# VIDCEnhancer.net
KiCad netlist of a schematic drawn in EAGLE
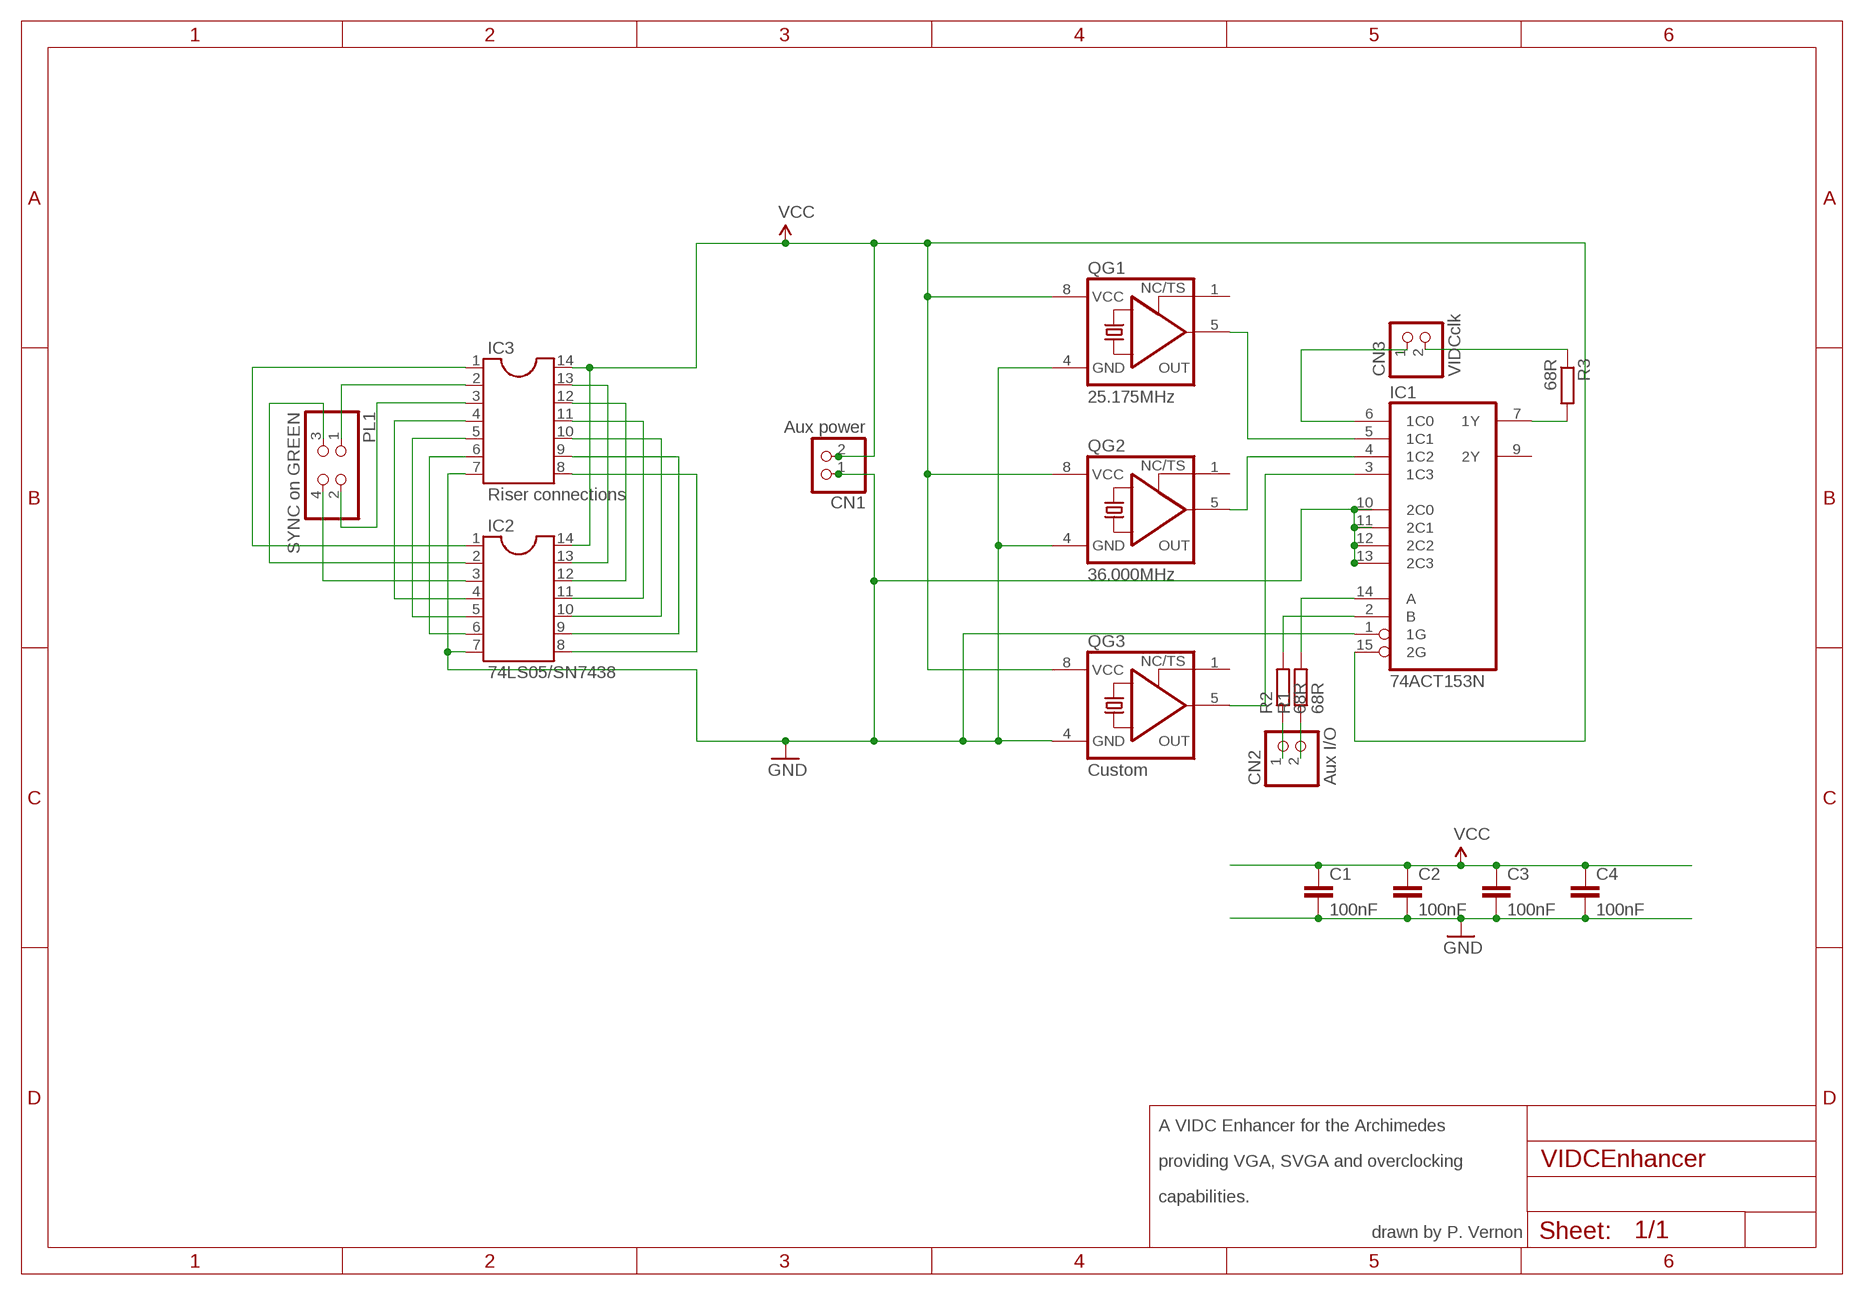
[diagram p0: schematic, sheet 1]

(export (version "E")
  (design (tool "Eeschema 10.0.6"))
  (components
    (comp (ref "C1")
      (value "100nF")
      (footprint "eagle-import:C025-025X050")
      (libsource (lib "eagle-import") (part "C-EU025-025X050"))
    )
    (comp (ref "C2")
      (value "100nF")
      (footprint "eagle-import:C025-025X050")
      (libsource (lib "eagle-import") (part "C-EU025-025X050"))
    )
    (comp (ref "C3")
      (value "100nF")
      (footprint "eagle-import:C025-025X050")
      (libsource (lib "eagle-import") (part "C-EU025-025X050"))
    )
    (comp (ref "C4")
      (value "100nF")
      (footprint "eagle-import:C025-025X050")
      (libsource (lib "eagle-import") (part "C-EU025-025X050"))
    )
    (comp (ref "CN1")
      (value "Aux power")
      (footprint "eagle-import:1X02_90")
      (libsource (lib "eagle-import") (part "PINHD-1X2/90"))
    )
    (comp (ref "CN2")
      (value "Aux I/O")
      (footprint "eagle-import:1X02_90")
      (libsource (lib "eagle-import") (part "PINHD-1X2/90"))
    )
    (comp (ref "CN3")
      (value "VIDCclk")
      (footprint "eagle-import:1X02_90")
      (libsource (lib "eagle-import") (part "PINHD-1X2/90"))
    )
    (comp (ref "IC1")
      (value "74ACT153N")
      (footprint "eagle-import:DIL16")
      (libsource (lib "eagle-import") (part "74153NACT"))
    )
    (comp (ref "IC2")
      (value "74LS05/SN7438")
      (footprint "eagle-import:SOCKET-14")
      (libsource (lib "eagle-import") (part "DIL14S"))
    )
    (comp (ref "IC3")
      (value "Riser connections")
      (footprint "eagle-import:SOCKET-14")
      (libsource (lib "eagle-import") (part "DIL14S"))
    )
    (comp (ref "PL1")
      (value "SYNC on GREEN")
      (footprint "eagle-import:2X02")
      (libsource (lib "eagle-import") (part "PINHD-2X2"))
    )
    (comp (ref "QG1")
      (value "25.175MHz")
      (footprint "eagle-import:DIL08S")
      (libsource (lib "eagle-import") (part "XO-8"))
    )
    (comp (ref "QG2")
      (value "36.000MHz")
      (footprint "eagle-import:DIL08S")
      (libsource (lib "eagle-import") (part "XO-8"))
    )
    (comp (ref "QG3")
      (value "Custom")
      (footprint "eagle-import:DIL08S")
      (libsource (lib "eagle-import") (part "XO-8"))
    )
    (comp (ref "R1")
      (value "68R")
      (footprint "eagle-import:0207_10")
      (libsource (lib "eagle-import") (part "R-EU_0207/10"))
    )
    (comp (ref "R2")
      (value "68R")
      (footprint "eagle-import:0207_10")
      (libsource (lib "eagle-import") (part "R-EU_0207/10"))
    )
    (comp (ref "R3")
      (value "68R")
      (footprint "eagle-import:0207_10")
      (libsource (lib "eagle-import") (part "R-EU_0207/10"))
    )
  )
  (nets
    (net (code "1") (name "GND") (class "Default")
      (node (ref "C1") (pin "2") (pinfunction "2_2") (pintype "passive"))
      (node (ref "C2") (pin "2") (pinfunction "2_2") (pintype "passive"))
      (node (ref "C3") (pin "2") (pinfunction "2_2") (pintype "passive"))
      (node (ref "C4") (pin "2") (pinfunction "2_2") (pintype "passive"))
      (node (ref "CN1") (pin "1") (pinfunction "1_1") (pintype "passive"))
      (node (ref "IC1") (pin "1") (pinfunction "1G_1") (pintype "input"))
      (node (ref "IC1") (pin "10") (pinfunction "2C0_10") (pintype "input"))
      (node (ref "IC1") (pin "11") (pinfunction "2C1_11") (pintype "input"))
      (node (ref "IC1") (pin "12") (pinfunction "2C2_12") (pintype "input"))
      (node (ref "IC1") (pin "13") (pinfunction "2C3_13") (pintype "input"))
      (node (ref "IC2") (pin "7") (pinfunction "7_7") (pintype "passive"))
      (node (ref "IC3") (pin "7") (pinfunction "7_7") (pintype "passive"))
      (node (ref "QG1") (pin "4") (pinfunction "GND_4") (pintype "power_in"))
      (node (ref "QG2") (pin "4") (pinfunction "GND_4") (pintype "power_in"))
      (node (ref "QG3") (pin "4") (pinfunction "GND_4") (pintype "power_in"))
    )
    (net (code "2") (name "Net-(CN2-Pad1)") (class "Default")
      (node (ref "CN2") (pin "1") (pinfunction "1_1") (pintype "passive"))
      (node (ref "R2") (pin "1") (pinfunction "1_1") (pintype "passive"))
    )
    (net (code "3") (name "Net-(CN2-Pad2)") (class "Default")
      (node (ref "CN2") (pin "2") (pinfunction "2_2") (pintype "passive"))
      (node (ref "R1") (pin "1") (pinfunction "1_1") (pintype "passive"))
    )
    (net (code "4") (name "Net-(CN3-Pad2)") (class "Default")
      (node (ref "CN3") (pin "2") (pinfunction "2_2") (pintype "passive"))
      (node (ref "R3") (pin "1") (pinfunction "1_1") (pintype "passive"))
    )
    (net (code "5") (name "Net-(IC1A-1C0)") (class "Default")
      (node (ref "CN3") (pin "1") (pinfunction "1_1") (pintype "passive"))
      (node (ref "IC1") (pin "6") (pinfunction "1C0_6") (pintype "input"))
    )
    (net (code "6") (name "Net-(IC1A-1C1)") (class "Default")
      (node (ref "IC1") (pin "5") (pinfunction "1C1_5") (pintype "input"))
      (node (ref "QG1") (pin "5") (pinfunction "OUT_5") (pintype "output"))
    )
    (net (code "7") (name "Net-(IC1A-1C2)") (class "Default")
      (node (ref "IC1") (pin "4") (pinfunction "1C2_4") (pintype "input"))
      (node (ref "QG2") (pin "5") (pinfunction "OUT_5") (pintype "output"))
    )
    (net (code "8") (name "Net-(IC1A-1C3)") (class "Default")
      (node (ref "IC1") (pin "3") (pinfunction "1C3_3") (pintype "input"))
      (node (ref "QG3") (pin "5") (pinfunction "OUT_5") (pintype "output"))
    )
    (net (code "9") (name "Net-(IC1A-1Y)") (class "Default")
      (node (ref "IC1") (pin "7") (pinfunction "1Y_7") (pintype "output"))
      (node (ref "R3") (pin "2") (pinfunction "2_2") (pintype "passive"))
    )
    (net (code "10") (name "Net-(IC1A-A)") (class "Default")
      (node (ref "IC1") (pin "14") (pinfunction "A_14") (pintype "input"))
      (node (ref "R1") (pin "2") (pinfunction "2_2") (pintype "passive"))
    )
    (net (code "11") (name "Net-(IC1A-B)") (class "Default")
      (node (ref "IC1") (pin "2") (pinfunction "B_2") (pintype "input"))
      (node (ref "R2") (pin "2") (pinfunction "2_2") (pintype "passive"))
    )
    (net (code "12") (name "Net-(IC2-Pad1)") (class "Default")
      (node (ref "IC2") (pin "1") (pinfunction "1_1") (pintype "passive"))
      (node (ref "IC3") (pin "1") (pinfunction "1_1") (pintype "passive"))
    )
    (net (code "13") (name "Net-(IC2-Pad2)") (class "Default")
      (node (ref "IC2") (pin "2") (pinfunction "2_2") (pintype "passive"))
      (node (ref "PL1") (pin "3") (pinfunction "3_3") (pintype "passive"))
    )
    (net (code "14") (name "Net-(IC2-Pad3)") (class "Default")
      (node (ref "IC2") (pin "3") (pinfunction "3_3") (pintype "passive"))
      (node (ref "PL1") (pin "4") (pinfunction "4_4") (pintype "passive"))
    )
    (net (code "15") (name "Net-(IC2-Pad4)") (class "Default")
      (node (ref "IC2") (pin "4") (pinfunction "4_4") (pintype "passive"))
      (node (ref "IC3") (pin "4") (pinfunction "4_4") (pintype "passive"))
    )
    (net (code "16") (name "Net-(IC2-Pad5)") (class "Default")
      (node (ref "IC2") (pin "5") (pinfunction "5_5") (pintype "passive"))
      (node (ref "IC3") (pin "5") (pinfunction "5_5") (pintype "passive"))
    )
    (net (code "17") (name "Net-(IC2-Pad6)") (class "Default")
      (node (ref "IC2") (pin "6") (pinfunction "6_6") (pintype "passive"))
      (node (ref "IC3") (pin "6") (pinfunction "6_6") (pintype "passive"))
    )
    (net (code "18") (name "Net-(IC2-Pad8)") (class "Default")
      (node (ref "IC2") (pin "8") (pinfunction "8_8") (pintype "passive"))
      (node (ref "IC3") (pin "8") (pinfunction "8_8") (pintype "passive"))
    )
    (net (code "19") (name "Net-(IC2-Pad9)") (class "Default")
      (node (ref "IC2") (pin "9") (pinfunction "9_9") (pintype "passive"))
      (node (ref "IC3") (pin "9") (pinfunction "9_9") (pintype "passive"))
    )
    (net (code "20") (name "Net-(IC2-Pad10)") (class "Default")
      (node (ref "IC2") (pin "10") (pinfunction "10_10") (pintype "passive"))
      (node (ref "IC3") (pin "10") (pinfunction "10_10") (pintype "passive"))
    )
    (net (code "21") (name "Net-(IC2-Pad11)") (class "Default")
      (node (ref "IC2") (pin "11") (pinfunction "11_11") (pintype "passive"))
      (node (ref "IC3") (pin "11") (pinfunction "11_11") (pintype "passive"))
    )
    (net (code "22") (name "Net-(IC2-Pad12)") (class "Default")
      (node (ref "IC2") (pin "12") (pinfunction "12_12") (pintype "passive"))
      (node (ref "IC3") (pin "12") (pinfunction "12_12") (pintype "passive"))
    )
    (net (code "23") (name "Net-(IC2-Pad13)") (class "Default")
      (node (ref "IC2") (pin "13") (pinfunction "13_13") (pintype "passive"))
      (node (ref "IC3") (pin "13") (pinfunction "13_13") (pintype "passive"))
    )
    (net (code "24") (name "Net-(IC3-Pad2)") (class "Default")
      (node (ref "IC3") (pin "2") (pinfunction "2_2") (pintype "passive"))
      (node (ref "PL1") (pin "1") (pinfunction "1_1") (pintype "passive"))
    )
    (net (code "25") (name "Net-(IC3-Pad3)") (class "Default")
      (node (ref "IC3") (pin "3") (pinfunction "3_3") (pintype "passive"))
      (node (ref "PL1") (pin "2") (pinfunction "2_2") (pintype "passive"))
    )
    (net (code "26") (name "VCC") (class "Default")
      (node (ref "C1") (pin "1") (pinfunction "1_1") (pintype "passive"))
      (node (ref "C2") (pin "1") (pinfunction "1_1") (pintype "passive"))
      (node (ref "C3") (pin "1") (pinfunction "1_1") (pintype "passive"))
      (node (ref "C4") (pin "1") (pinfunction "1_1") (pintype "passive"))
      (node (ref "CN1") (pin "2") (pinfunction "2_2") (pintype "passive"))
      (node (ref "IC1") (pin "15") (pinfunction "2G_15") (pintype "input"))
      (node (ref "IC2") (pin "14") (pinfunction "14_14") (pintype "passive"))
      (node (ref "IC3") (pin "14") (pinfunction "14_14") (pintype "passive"))
      (node (ref "QG1") (pin "8") (pinfunction "VCC_8") (pintype "power_in"))
      (node (ref "QG2") (pin "8") (pinfunction "VCC_8") (pintype "power_in"))
      (node (ref "QG3") (pin "8") (pinfunction "VCC_8") (pintype "power_in"))
    )
    (net (code "27") (name "unconnected-(IC1A-2Y-Pad9)") (class "Default")
      (node (ref "IC1") (pin "9") (pinfunction "2Y_9") (pintype "output"))
    )
    (net (code "28") (name "unconnected-(QG1-TS-Pad1)") (class "Default")
      (node (ref "QG1") (pin "1") (pinfunction "TS_1") (pintype "passive"))
    )
    (net (code "29") (name "unconnected-(QG2-TS-Pad1)") (class "Default")
      (node (ref "QG2") (pin "1") (pinfunction "TS_1") (pintype "passive"))
    )
    (net (code "30") (name "unconnected-(QG3-TS-Pad1)") (class "Default")
      (node (ref "QG3") (pin "1") (pinfunction "TS_1") (pintype "passive"))
    )
  )
)
